# design.net
KiCad netlist of a schematic drawn in EAGLE
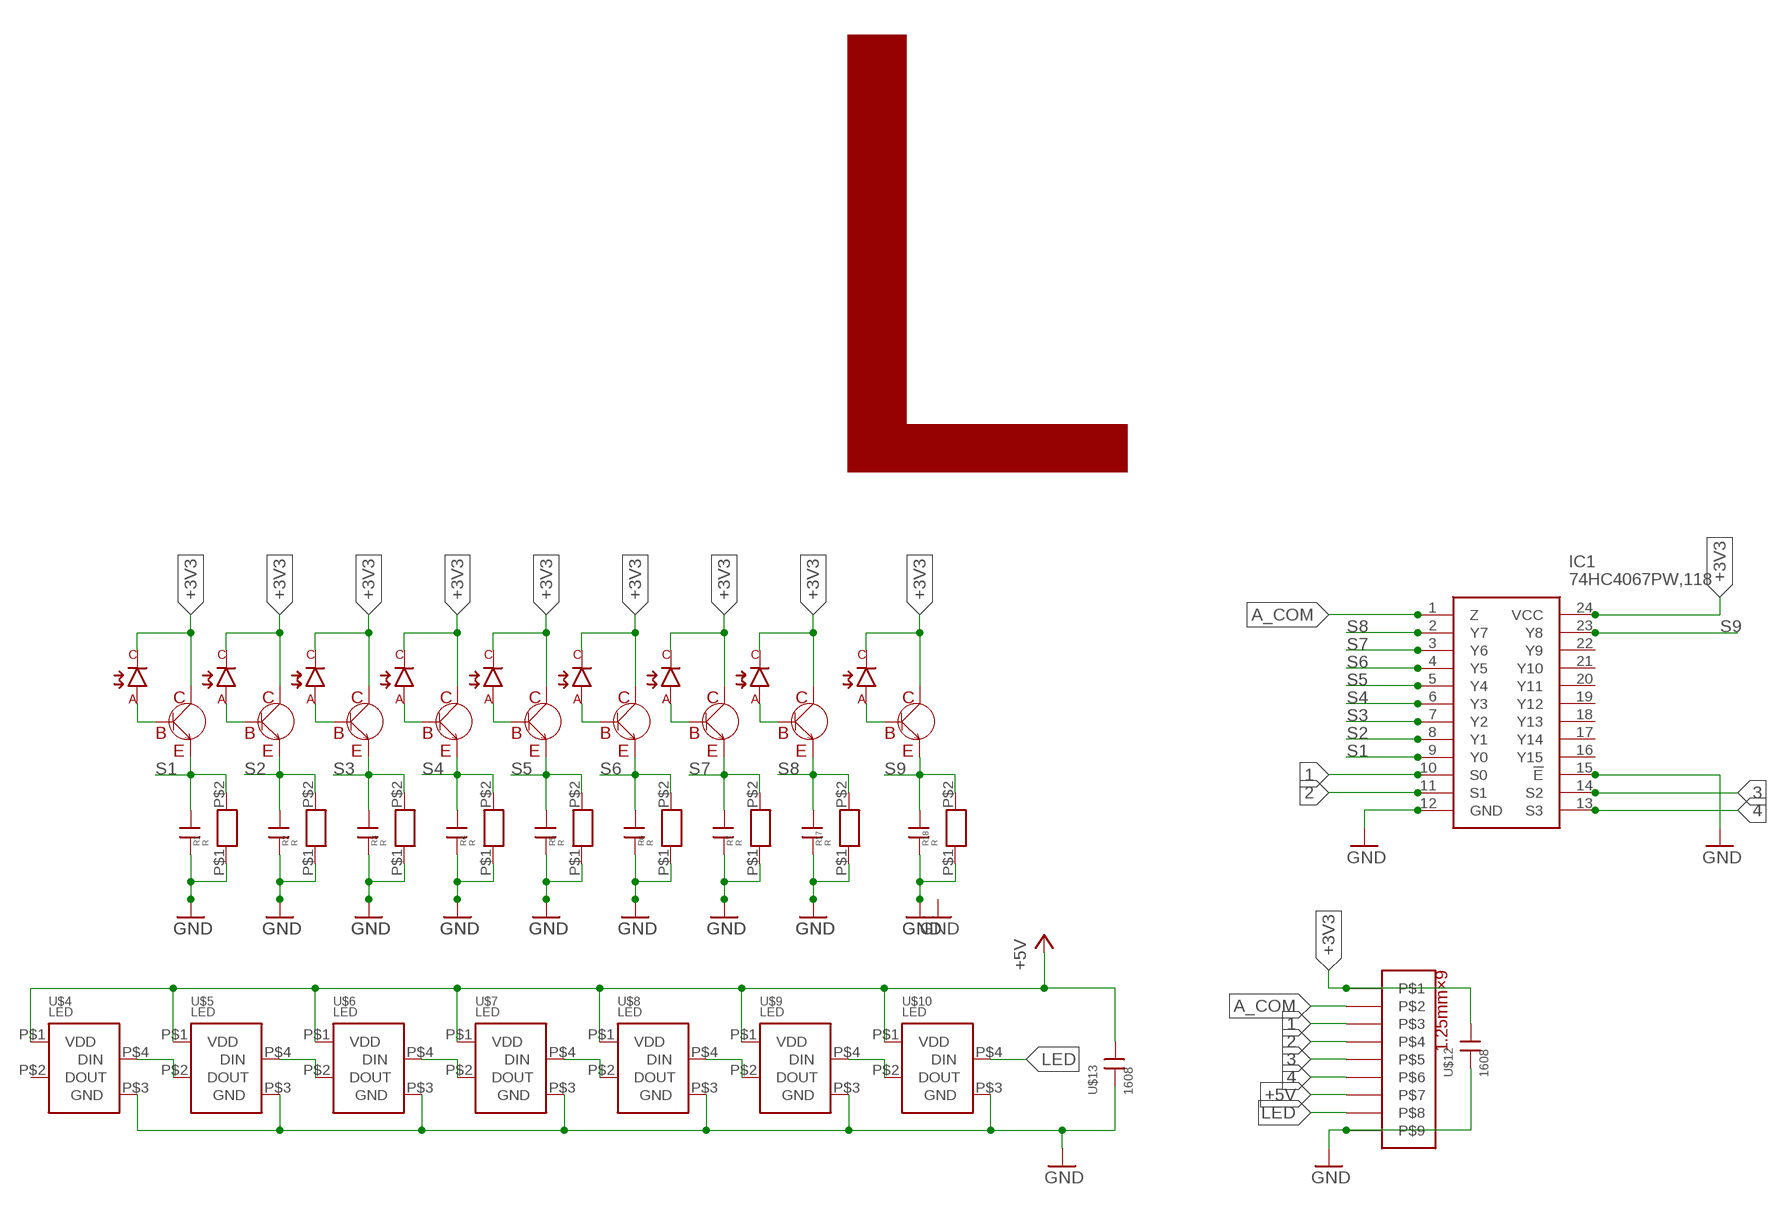
[diagram p0: schematic, sheet 1]

(export (version "E")
  (design (tool "Eeschema 10.0.6"))
  (components
    (comp (ref "C1")
      (value "1608")
      (footprint "eagle-import:CON")
      (libsource (lib "eagle-import") (part "1608"))
    )
    (comp (ref "C2")
      (value "1608")
      (footprint "eagle-import:CON")
      (libsource (lib "eagle-import") (part "1608"))
    )
    (comp (ref "C3")
      (value "1608")
      (footprint "eagle-import:CON")
      (libsource (lib "eagle-import") (part "1608"))
    )
    (comp (ref "C4")
      (value "1608")
      (footprint "eagle-import:CON")
      (libsource (lib "eagle-import") (part "1608"))
    )
    (comp (ref "C5")
      (value "1608")
      (footprint "eagle-import:CON")
      (libsource (lib "eagle-import") (part "1608"))
    )
    (comp (ref "C6")
      (value "1608")
      (footprint "eagle-import:CON")
      (libsource (lib "eagle-import") (part "1608"))
    )
    (comp (ref "C7")
      (value "1608")
      (footprint "eagle-import:CON")
      (libsource (lib "eagle-import") (part "1608"))
    )
    (comp (ref "C17")
      (value "1608")
      (footprint "eagle-import:CON")
      (libsource (lib "eagle-import") (part "1608"))
    )
    (comp (ref "C18")
      (value "1608")
      (footprint "eagle-import:CON")
      (libsource (lib "eagle-import") (part "1608"))
    )
    (comp (ref "IC1")
      (value "74HC4067PW,118")
      (footprint "eagle-import:SOP65P640X110-24N")
      (fields (field (name "MOUSER_PART_NUMBER") "771-74HC4067PW-T"))
      (libsource (lib "eagle-import") (part "74HC4067PW,118"))
    )
    (comp (ref "R1") (value "R") (footprint "eagle-import:1608") (libsource (lib "eagle-import") (part "R")))
    (comp (ref "R2") (value "R") (footprint "eagle-import:1608") (libsource (lib "eagle-import") (part "R")))
    (comp (ref "R3") (value "R") (footprint "eagle-import:1608") (libsource (lib "eagle-import") (part "R")))
    (comp (ref "R4") (value "R") (footprint "eagle-import:1608") (libsource (lib "eagle-import") (part "R")))
    (comp (ref "R5") (value "R") (footprint "eagle-import:1608") (libsource (lib "eagle-import") (part "R")))
    (comp (ref "R6") (value "R") (footprint "eagle-import:1608") (libsource (lib "eagle-import") (part "R")))
    (comp (ref "R7") (value "R") (footprint "eagle-import:1608") (libsource (lib "eagle-import") (part "R")))
    (comp (ref "R17") (value "R") (footprint "eagle-import:1608") (libsource (lib "eagle-import") (part "R")))
    (comp (ref "R18") (value "R") (footprint "eagle-import:1608") (libsource (lib "eagle-import") (part "R")))
    (comp (ref "U$4")
      (value "LED")
      (footprint "eagle-import:LED")
      (libsource (lib "eagle-import") (part "LED"))
    )
    (comp (ref "U$5")
      (value "LED")
      (footprint "eagle-import:LED")
      (libsource (lib "eagle-import") (part "LED"))
    )
    (comp (ref "U$6")
      (value "LED")
      (footprint "eagle-import:LED")
      (libsource (lib "eagle-import") (part "LED"))
    )
    (comp (ref "U$7")
      (value "LED")
      (footprint "eagle-import:LED")
      (libsource (lib "eagle-import") (part "LED"))
    )
    (comp (ref "U$8")
      (value "LED")
      (footprint "eagle-import:LED")
      (libsource (lib "eagle-import") (part "LED"))
    )
    (comp (ref "U$9")
      (value "LED")
      (footprint "eagle-import:LED")
      (libsource (lib "eagle-import") (part "LED"))
    )
    (comp (ref "U$10")
      (value "LED")
      (footprint "eagle-import:LED")
      (libsource (lib "eagle-import") (part "LED"))
    )
    (comp (ref "U$11")
      (value "1MMCON")
      (footprint "eagle-import:1MMCON")
      (libsource (lib "eagle-import") (part "1MMCON"))
    )
    (comp (ref "U$12")
      (value "1608")
      (footprint "eagle-import:CON")
      (libsource (lib "eagle-import") (part "1608"))
    )
    (comp (ref "U$13")
      (value "1608")
      (footprint "eagle-import:CON")
      (libsource (lib "eagle-import") (part "1608"))
    )
    (comp (ref "U$14")
      (value "2CS2712")
      (footprint "eagle-import:TRANS_SSM3J325F,LF")
      (libsource (lib "eagle-import") (part "2CS2712"))
    )
    (comp (ref "U$15")
      (value "フォトダイオード")
      (footprint "eagle-import:フォトダイオード")
      (libsource (lib "eagle-import") (part "フォトダイオード"))
    )
    (comp (ref "U$16")
      (value "2CS2712")
      (footprint "eagle-import:TRANS_SSM3J325F,LF")
      (libsource (lib "eagle-import") (part "2CS2712"))
    )
    (comp (ref "U$17")
      (value "フォトダイオード")
      (footprint "eagle-import:フォトダイオード")
      (libsource (lib "eagle-import") (part "フォトダイオード"))
    )
    (comp (ref "U$18")
      (value "2CS2712")
      (footprint "eagle-import:TRANS_SSM3J325F,LF")
      (libsource (lib "eagle-import") (part "2CS2712"))
    )
    (comp (ref "U$19")
      (value "フォトダイオード")
      (footprint "eagle-import:フォトダイオード")
      (libsource (lib "eagle-import") (part "フォトダイオード"))
    )
    (comp (ref "U$20")
      (value "2CS2712")
      (footprint "eagle-import:TRANS_SSM3J325F,LF")
      (libsource (lib "eagle-import") (part "2CS2712"))
    )
    (comp (ref "U$21")
      (value "フォトダイオード")
      (footprint "eagle-import:フォトダイオード")
      (libsource (lib "eagle-import") (part "フォトダイオード"))
    )
    (comp (ref "U$22")
      (value "2CS2712")
      (footprint "eagle-import:TRANS_SSM3J325F,LF")
      (libsource (lib "eagle-import") (part "2CS2712"))
    )
    (comp (ref "U$23")
      (value "フォトダイオード")
      (footprint "eagle-import:フォトダイオード")
      (libsource (lib "eagle-import") (part "フォトダイオード"))
    )
    (comp (ref "U$24")
      (value "2CS2712")
      (footprint "eagle-import:TRANS_SSM3J325F,LF")
      (libsource (lib "eagle-import") (part "2CS2712"))
    )
    (comp (ref "U$25")
      (value "フォトダイオード")
      (footprint "eagle-import:フォトダイオード")
      (libsource (lib "eagle-import") (part "フォトダイオード"))
    )
    (comp (ref "U$26")
      (value "2CS2712")
      (footprint "eagle-import:TRANS_SSM3J325F,LF")
      (libsource (lib "eagle-import") (part "2CS2712"))
    )
    (comp (ref "U$27")
      (value "フォトダイオード")
      (footprint "eagle-import:フォトダイオード")
      (libsource (lib "eagle-import") (part "フォトダイオード"))
    )
    (comp (ref "U$28")
      (value "2CS2712")
      (footprint "eagle-import:TRANS_SSM3J325F,LF")
      (libsource (lib "eagle-import") (part "2CS2712"))
    )
    (comp (ref "U$29")
      (value "フォトダイオード")
      (footprint "eagle-import:フォトダイオード")
      (libsource (lib "eagle-import") (part "フォトダイオード"))
    )
    (comp (ref "U$30")
      (value "2CS2712")
      (footprint "eagle-import:TRANS_SSM3J325F,LF")
      (libsource (lib "eagle-import") (part "2CS2712"))
    )
    (comp (ref "U$31")
      (value "フォトダイオード")
      (footprint "eagle-import:フォトダイオード")
      (libsource (lib "eagle-import") (part "フォトダイオード"))
    )
  )
  (nets
    (net (code "1") (name "+3V3") (class "Default")
      (node (ref "IC1") (pin "24") (pinfunction "VCC_24") (pintype "bidirectional"))
      (node (ref "U$11") (pin "P$1") (pinfunction "P$1_P$1") (pintype "bidirectional"))
      (node (ref "U$12") (pin "P$1") (pinfunction "1_P$1") (pintype "bidirectional"))
      (node (ref "U$14") (pin "C") (pinfunction "C_C") (pintype "bidirectional"))
      (node (ref "U$15") (pin "C") (pinfunction "C_C") (pintype "bidirectional"))
      (node (ref "U$16") (pin "C") (pinfunction "C_C") (pintype "bidirectional"))
      (node (ref "U$17") (pin "C") (pinfunction "C_C") (pintype "bidirectional"))
      (node (ref "U$18") (pin "C") (pinfunction "C_C") (pintype "bidirectional"))
      (node (ref "U$19") (pin "C") (pinfunction "C_C") (pintype "bidirectional"))
      (node (ref "U$20") (pin "C") (pinfunction "C_C") (pintype "bidirectional"))
      (node (ref "U$21") (pin "C") (pinfunction "C_C") (pintype "bidirectional"))
      (node (ref "U$22") (pin "C") (pinfunction "C_C") (pintype "bidirectional"))
      (node (ref "U$23") (pin "C") (pinfunction "C_C") (pintype "bidirectional"))
      (node (ref "U$24") (pin "C") (pinfunction "C_C") (pintype "bidirectional"))
      (node (ref "U$25") (pin "C") (pinfunction "C_C") (pintype "bidirectional"))
      (node (ref "U$26") (pin "C") (pinfunction "C_C") (pintype "bidirectional"))
      (node (ref "U$27") (pin "C") (pinfunction "C_C") (pintype "bidirectional"))
      (node (ref "U$28") (pin "C") (pinfunction "C_C") (pintype "bidirectional"))
      (node (ref "U$29") (pin "C") (pinfunction "C_C") (pintype "bidirectional"))
      (node (ref "U$30") (pin "C") (pinfunction "C_C") (pintype "bidirectional"))
      (node (ref "U$31") (pin "C") (pinfunction "C_C") (pintype "bidirectional"))
    )
    (net (code "2") (name "+5V") (class "Default")
      (node (ref "U$10") (pin "P$1") (pinfunction "VDD_P$1") (pintype "bidirectional"))
      (node (ref "U$11") (pin "P$7") (pinfunction "P$7_P$7") (pintype "bidirectional"))
      (node (ref "U$13") (pin "P$1") (pinfunction "1_P$1") (pintype "bidirectional"))
      (node (ref "U$4") (pin "P$1") (pinfunction "VDD_P$1") (pintype "bidirectional"))
      (node (ref "U$5") (pin "P$1") (pinfunction "VDD_P$1") (pintype "bidirectional"))
      (node (ref "U$6") (pin "P$1") (pinfunction "VDD_P$1") (pintype "bidirectional"))
      (node (ref "U$7") (pin "P$1") (pinfunction "VDD_P$1") (pintype "bidirectional"))
      (node (ref "U$8") (pin "P$1") (pinfunction "VDD_P$1") (pintype "bidirectional"))
      (node (ref "U$9") (pin "P$1") (pinfunction "VDD_P$1") (pintype "bidirectional"))
    )
    (net (code "3") (name "/S1") (class "Default")
      (node (ref "C1") (pin "P$1") (pinfunction "1_P$1") (pintype "bidirectional"))
      (node (ref "IC1") (pin "9") (pinfunction "Y0_9") (pintype "bidirectional"))
      (node (ref "R1") (pin "P$2") (pinfunction "P$2_P$2") (pintype "bidirectional"))
      (node (ref "U$14") (pin "E") (pinfunction "E_E") (pintype "bidirectional"))
    )
    (net (code "4") (name "/S2") (class "Default")
      (node (ref "C2") (pin "P$1") (pinfunction "1_P$1") (pintype "bidirectional"))
      (node (ref "IC1") (pin "8") (pinfunction "Y1_8") (pintype "bidirectional"))
      (node (ref "R2") (pin "P$2") (pinfunction "P$2_P$2") (pintype "bidirectional"))
      (node (ref "U$16") (pin "E") (pinfunction "E_E") (pintype "bidirectional"))
    )
    (net (code "5") (name "/S3") (class "Default")
      (node (ref "C3") (pin "P$1") (pinfunction "1_P$1") (pintype "bidirectional"))
      (node (ref "IC1") (pin "7") (pinfunction "Y2_7") (pintype "bidirectional"))
      (node (ref "R3") (pin "P$2") (pinfunction "P$2_P$2") (pintype "bidirectional"))
      (node (ref "U$18") (pin "E") (pinfunction "E_E") (pintype "bidirectional"))
    )
    (net (code "6") (name "/S4") (class "Default")
      (node (ref "C4") (pin "P$1") (pinfunction "1_P$1") (pintype "bidirectional"))
      (node (ref "IC1") (pin "6") (pinfunction "Y3_6") (pintype "bidirectional"))
      (node (ref "R4") (pin "P$2") (pinfunction "P$2_P$2") (pintype "bidirectional"))
      (node (ref "U$20") (pin "E") (pinfunction "E_E") (pintype "bidirectional"))
    )
    (net (code "7") (name "/S5") (class "Default")
      (node (ref "C5") (pin "P$1") (pinfunction "1_P$1") (pintype "bidirectional"))
      (node (ref "IC1") (pin "5") (pinfunction "Y4_5") (pintype "bidirectional"))
      (node (ref "R5") (pin "P$2") (pinfunction "P$2_P$2") (pintype "bidirectional"))
      (node (ref "U$22") (pin "E") (pinfunction "E_E") (pintype "bidirectional"))
    )
    (net (code "8") (name "/S6") (class "Default")
      (node (ref "C6") (pin "P$1") (pinfunction "1_P$1") (pintype "bidirectional"))
      (node (ref "IC1") (pin "4") (pinfunction "Y5_4") (pintype "bidirectional"))
      (node (ref "R6") (pin "P$2") (pinfunction "P$2_P$2") (pintype "bidirectional"))
      (node (ref "U$24") (pin "E") (pinfunction "E_E") (pintype "bidirectional"))
    )
    (net (code "9") (name "/S7") (class "Default")
      (node (ref "C7") (pin "P$1") (pinfunction "1_P$1") (pintype "bidirectional"))
      (node (ref "IC1") (pin "3") (pinfunction "Y6_3") (pintype "bidirectional"))
      (node (ref "R7") (pin "P$2") (pinfunction "P$2_P$2") (pintype "bidirectional"))
      (node (ref "U$26") (pin "E") (pinfunction "E_E") (pintype "bidirectional"))
    )
    (net (code "10") (name "/S8") (class "Default")
      (node (ref "C17") (pin "P$1") (pinfunction "1_P$1") (pintype "bidirectional"))
      (node (ref "IC1") (pin "2") (pinfunction "Y7_2") (pintype "bidirectional"))
      (node (ref "R17") (pin "P$2") (pinfunction "P$2_P$2") (pintype "bidirectional"))
      (node (ref "U$28") (pin "E") (pinfunction "E_E") (pintype "bidirectional"))
    )
    (net (code "11") (name "/S9") (class "Default")
      (node (ref "C18") (pin "P$1") (pinfunction "1_P$1") (pintype "bidirectional"))
      (node (ref "IC1") (pin "23") (pinfunction "Y8_23") (pintype "bidirectional"))
      (node (ref "R18") (pin "P$2") (pinfunction "P$2_P$2") (pintype "bidirectional"))
      (node (ref "U$30") (pin "E") (pinfunction "E_E") (pintype "bidirectional"))
    )
    (net (code "12") (name "1") (class "Default")
      (node (ref "IC1") (pin "10") (pinfunction "S0_10") (pintype "bidirectional"))
      (node (ref "U$11") (pin "P$3") (pinfunction "P$3_P$3") (pintype "bidirectional"))
    )
    (net (code "13") (name "2") (class "Default")
      (node (ref "IC1") (pin "11") (pinfunction "S1_11") (pintype "bidirectional"))
      (node (ref "U$11") (pin "P$4") (pinfunction "P$4_P$4") (pintype "bidirectional"))
    )
    (net (code "14") (name "3") (class "Default")
      (node (ref "IC1") (pin "14") (pinfunction "S2_14") (pintype "bidirectional"))
      (node (ref "U$11") (pin "P$5") (pinfunction "P$5_P$5") (pintype "bidirectional"))
    )
    (net (code "15") (name "4") (class "Default")
      (node (ref "IC1") (pin "13") (pinfunction "S3_13") (pintype "bidirectional"))
      (node (ref "U$11") (pin "P$6") (pinfunction "P$6_P$6") (pintype "bidirectional"))
    )
    (net (code "16") (name "A_COM") (class "Default")
      (node (ref "IC1") (pin "1") (pinfunction "Z_1") (pintype "bidirectional"))
      (node (ref "U$11") (pin "P$2") (pinfunction "P$2_P$2") (pintype "bidirectional"))
    )
    (net (code "17") (name "GND") (class "Default")
      (node (ref "C1") (pin "P$2") (pinfunction "2_P$2") (pintype "bidirectional"))
      (node (ref "C17") (pin "P$2") (pinfunction "2_P$2") (pintype "bidirectional"))
      (node (ref "C18") (pin "P$2") (pinfunction "2_P$2") (pintype "bidirectional"))
      (node (ref "C2") (pin "P$2") (pinfunction "2_P$2") (pintype "bidirectional"))
      (node (ref "C3") (pin "P$2") (pinfunction "2_P$2") (pintype "bidirectional"))
      (node (ref "C4") (pin "P$2") (pinfunction "2_P$2") (pintype "bidirectional"))
      (node (ref "C5") (pin "P$2") (pinfunction "2_P$2") (pintype "bidirectional"))
      (node (ref "C6") (pin "P$2") (pinfunction "2_P$2") (pintype "bidirectional"))
      (node (ref "C7") (pin "P$2") (pinfunction "2_P$2") (pintype "bidirectional"))
      (node (ref "IC1") (pin "12") (pinfunction "GND_12") (pintype "bidirectional"))
      (node (ref "IC1") (pin "15") (pinfunction "~{E}_15") (pintype "bidirectional"))
      (node (ref "R1") (pin "P$1") (pinfunction "P$1_P$1") (pintype "bidirectional"))
      (node (ref "R17") (pin "P$1") (pinfunction "P$1_P$1") (pintype "bidirectional"))
      (node (ref "R18") (pin "P$1") (pinfunction "P$1_P$1") (pintype "bidirectional"))
      (node (ref "R2") (pin "P$1") (pinfunction "P$1_P$1") (pintype "bidirectional"))
      (node (ref "R3") (pin "P$1") (pinfunction "P$1_P$1") (pintype "bidirectional"))
      (node (ref "R4") (pin "P$1") (pinfunction "P$1_P$1") (pintype "bidirectional"))
      (node (ref "R5") (pin "P$1") (pinfunction "P$1_P$1") (pintype "bidirectional"))
      (node (ref "R6") (pin "P$1") (pinfunction "P$1_P$1") (pintype "bidirectional"))
      (node (ref "R7") (pin "P$1") (pinfunction "P$1_P$1") (pintype "bidirectional"))
      (node (ref "U$10") (pin "P$3") (pinfunction "GND_P$3") (pintype "bidirectional"))
      (node (ref "U$11") (pin "P$9") (pinfunction "P$9_P$9") (pintype "bidirectional"))
      (node (ref "U$12") (pin "P$2") (pinfunction "2_P$2") (pintype "bidirectional"))
      (node (ref "U$13") (pin "P$2") (pinfunction "2_P$2") (pintype "bidirectional"))
      (node (ref "U$4") (pin "P$3") (pinfunction "GND_P$3") (pintype "bidirectional"))
      (node (ref "U$5") (pin "P$3") (pinfunction "GND_P$3") (pintype "bidirectional"))
      (node (ref "U$6") (pin "P$3") (pinfunction "GND_P$3") (pintype "bidirectional"))
      (node (ref "U$7") (pin "P$3") (pinfunction "GND_P$3") (pintype "bidirectional"))
      (node (ref "U$8") (pin "P$3") (pinfunction "GND_P$3") (pintype "bidirectional"))
      (node (ref "U$9") (pin "P$3") (pinfunction "GND_P$3") (pintype "bidirectional"))
    )
    (net (code "18") (name "LED") (class "Default")
      (node (ref "U$10") (pin "P$4") (pinfunction "DIN_P$4") (pintype "bidirectional"))
      (node (ref "U$11") (pin "P$8") (pinfunction "P$8_P$8") (pintype "bidirectional"))
    )
    (net (code "19") (name "Net-(U$4-DIN)") (class "Default")
      (node (ref "U$4") (pin "P$4") (pinfunction "DIN_P$4") (pintype "bidirectional"))
      (node (ref "U$5") (pin "P$2") (pinfunction "DOUT_P$2") (pintype "bidirectional"))
    )
    (net (code "20") (name "Net-(U$5-DIN)") (class "Default")
      (node (ref "U$5") (pin "P$4") (pinfunction "DIN_P$4") (pintype "bidirectional"))
      (node (ref "U$6") (pin "P$2") (pinfunction "DOUT_P$2") (pintype "bidirectional"))
    )
    (net (code "21") (name "Net-(U$6-DIN)") (class "Default")
      (node (ref "U$6") (pin "P$4") (pinfunction "DIN_P$4") (pintype "bidirectional"))
      (node (ref "U$7") (pin "P$2") (pinfunction "DOUT_P$2") (pintype "bidirectional"))
    )
    (net (code "22") (name "Net-(U$7-DIN)") (class "Default")
      (node (ref "U$7") (pin "P$4") (pinfunction "DIN_P$4") (pintype "bidirectional"))
      (node (ref "U$8") (pin "P$2") (pinfunction "DOUT_P$2") (pintype "bidirectional"))
    )
    (net (code "23") (name "Net-(U$8-DIN)") (class "Default")
      (node (ref "U$8") (pin "P$4") (pinfunction "DIN_P$4") (pintype "bidirectional"))
      (node (ref "U$9") (pin "P$2") (pinfunction "DOUT_P$2") (pintype "bidirectional"))
    )
    (net (code "24") (name "Net-(U$10-DOUT)") (class "Default")
      (node (ref "U$10") (pin "P$2") (pinfunction "DOUT_P$2") (pintype "bidirectional"))
      (node (ref "U$9") (pin "P$4") (pinfunction "DIN_P$4") (pintype "bidirectional"))
    )
    (net (code "25") (name "Net-(U$14-PadB)") (class "Default")
      (node (ref "U$14") (pin "B") (pinfunction "B_B") (pintype "bidirectional"))
      (node (ref "U$15") (pin "A") (pinfunction "A_A") (pintype "bidirectional"))
    )
    (net (code "26") (name "Net-(U$16-PadB)") (class "Default")
      (node (ref "U$16") (pin "B") (pinfunction "B_B") (pintype "bidirectional"))
      (node (ref "U$17") (pin "A") (pinfunction "A_A") (pintype "bidirectional"))
    )
    (net (code "27") (name "Net-(U$18-PadB)") (class "Default")
      (node (ref "U$18") (pin "B") (pinfunction "B_B") (pintype "bidirectional"))
      (node (ref "U$19") (pin "A") (pinfunction "A_A") (pintype "bidirectional"))
    )
    (net (code "28") (name "Net-(U$20-PadB)") (class "Default")
      (node (ref "U$20") (pin "B") (pinfunction "B_B") (pintype "bidirectional"))
      (node (ref "U$21") (pin "A") (pinfunction "A_A") (pintype "bidirectional"))
    )
    (net (code "29") (name "Net-(U$22-PadB)") (class "Default")
      (node (ref "U$22") (pin "B") (pinfunction "B_B") (pintype "bidirectional"))
      (node (ref "U$23") (pin "A") (pinfunction "A_A") (pintype "bidirectional"))
    )
    (net (code "30") (name "Net-(U$24-PadB)") (class "Default")
      (node (ref "U$24") (pin "B") (pinfunction "B_B") (pintype "bidirectional"))
      (node (ref "U$25") (pin "A") (pinfunction "A_A") (pintype "bidirectional"))
    )
    (net (code "31") (name "Net-(U$26-PadB)") (class "Default")
      (node (ref "U$26") (pin "B") (pinfunction "B_B") (pintype "bidirectional"))
      (node (ref "U$27") (pin "A") (pinfunction "A_A") (pintype "bidirectional"))
    )
    (net (code "32") (name "Net-(U$28-PadB)") (class "Default")
      (node (ref "U$28") (pin "B") (pinfunction "B_B") (pintype "bidirectional"))
      (node (ref "U$29") (pin "A") (pinfunction "A_A") (pintype "bidirectional"))
    )
    (net (code "33") (name "Net-(U$30-PadB)") (class "Default")
      (node (ref "U$30") (pin "B") (pinfunction "B_B") (pintype "bidirectional"))
      (node (ref "U$31") (pin "A") (pinfunction "A_A") (pintype "bidirectional"))
    )
    (net (code "34") (name "unconnected-(IC1-Y9-Pad22)") (class "Default")
      (node (ref "IC1") (pin "22") (pinfunction "Y9_22") (pintype "bidirectional"))
    )
    (net (code "35") (name "unconnected-(IC1-Y10-Pad21)") (class "Default")
      (node (ref "IC1") (pin "21") (pinfunction "Y10_21") (pintype "bidirectional"))
    )
    (net (code "36") (name "unconnected-(IC1-Y11-Pad20)") (class "Default")
      (node (ref "IC1") (pin "20") (pinfunction "Y11_20") (pintype "bidirectional"))
    )
    (net (code "37") (name "unconnected-(IC1-Y12-Pad19)") (class "Default")
      (node (ref "IC1") (pin "19") (pinfunction "Y12_19") (pintype "bidirectional"))
    )
    (net (code "38") (name "unconnected-(IC1-Y13-Pad18)") (class "Default")
      (node (ref "IC1") (pin "18") (pinfunction "Y13_18") (pintype "bidirectional"))
    )
    (net (code "39") (name "unconnected-(IC1-Y14-Pad17)") (class "Default")
      (node (ref "IC1") (pin "17") (pinfunction "Y14_17") (pintype "bidirectional"))
    )
    (net (code "40") (name "unconnected-(IC1-Y15-Pad16)") (class "Default")
      (node (ref "IC1") (pin "16") (pinfunction "Y15_16") (pintype "bidirectional"))
    )
    (net (code "41") (name "unconnected-(U$4-DOUT-PadP$2)") (class "Default")
      (node (ref "U$4") (pin "P$2") (pinfunction "DOUT_P$2") (pintype "bidirectional"))
    )
  )
)
